# Aptomat_power_supply.net
KiCad netlist of a schematic drawn in Altium Designer
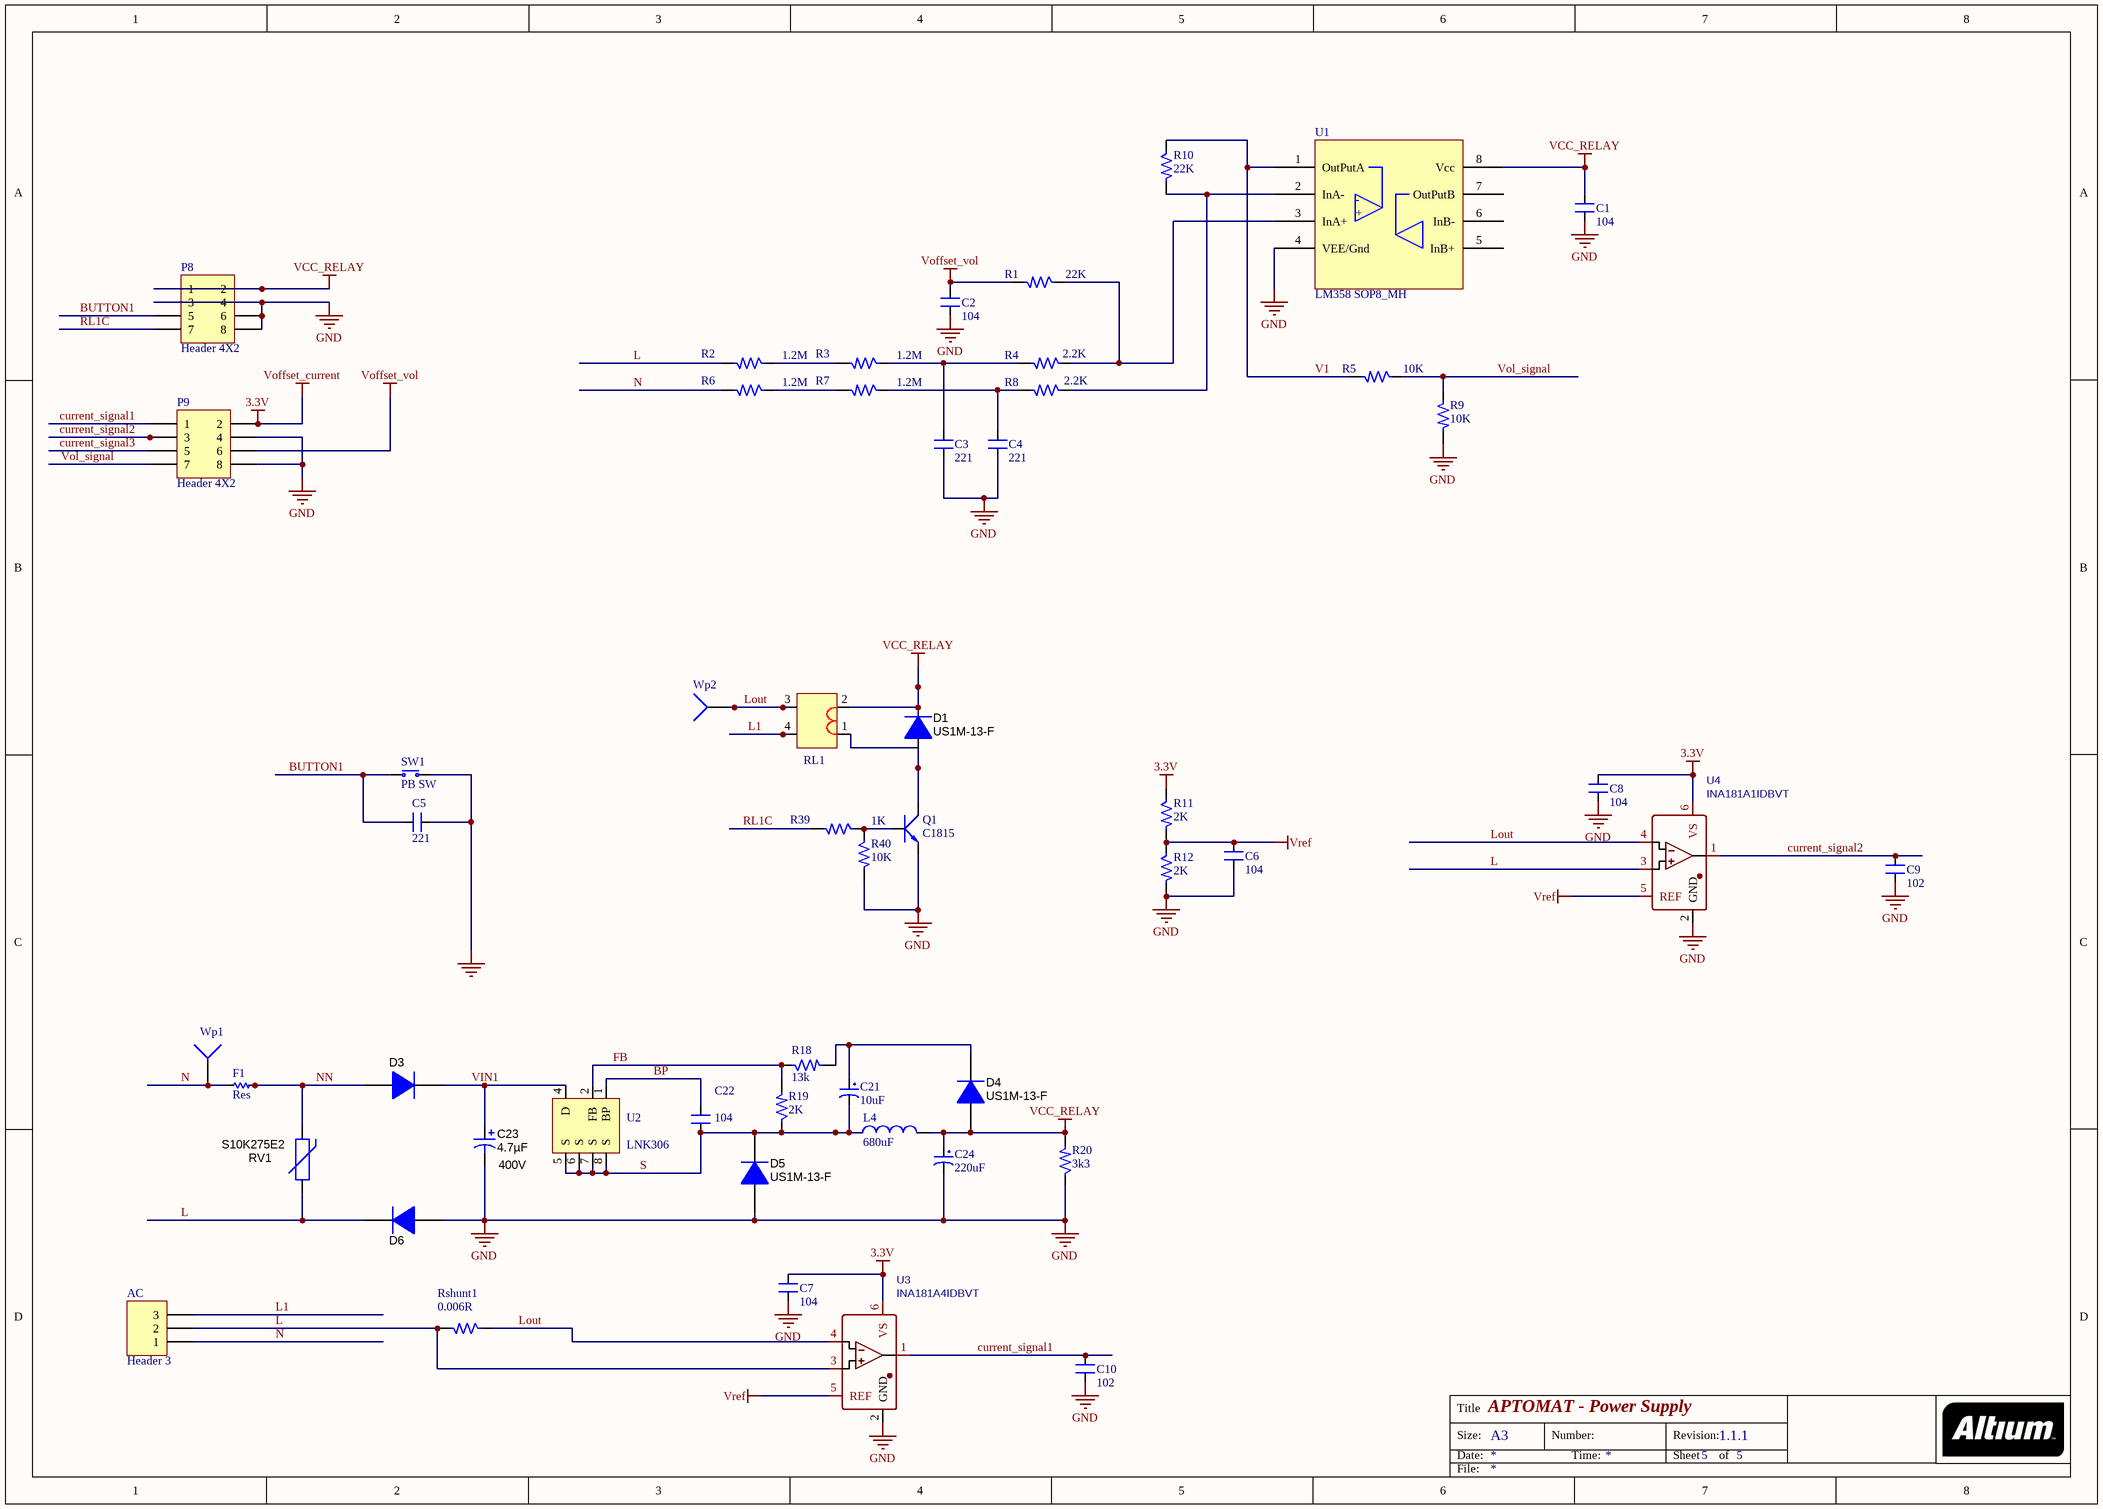
[diagram p0: Aptomat_power_supply.SchDoc]

(export (version "E")
  (design (tool "Eeschema 10.0.6"))
  (components
    (comp (ref "AC")
      (value "Header 3")
      (footprint "CHAN3DONG")
      (description "Header, 3-Pin")
      (fields (field (name "PUBLISHER") "Altium Limited"))
      (libsource (lib "Miscellaneous Connectors") (part "Header 3"))
    )
    (comp (ref "C1")
      (value "104")
      (footprint "0805_HV")
      (description "Cap SMD")
      (libsource (lib "hatcatbietbay") (part "CM"))
    )
    (comp (ref "C2")
      (value "104")
      (footprint "0805_HV")
      (description "Cap SMD")
      (libsource (lib "hatcatbietbay") (part "CM"))
    )
    (comp (ref "C3")
      (value "221")
      (footprint "0805_HV")
      (description "Cap SMD")
      (libsource (lib "hatcatbietbay") (part "CM"))
    )
    (comp (ref "C4")
      (value "221")
      (footprint "0805_HV")
      (description "Cap SMD")
      (libsource (lib "hatcatbietbay") (part "CM"))
    )
    (comp (ref "C5")
      (value "221")
      (footprint "0805_HV")
      (description "Cap SMD")
      (libsource (lib "hatcatbietbay") (part "CM"))
    )
    (comp (ref "C6")
      (value "104")
      (footprint "0805_HV")
      (description "Cap SMD")
      (libsource (lib "hatcatbietbay") (part "CM"))
    )
    (comp (ref "C7")
      (value "104")
      (footprint "0805_HV")
      (description "Cap SMD")
      (libsource (lib "hatcatbietbay") (part "CM"))
    )
    (comp (ref "C8")
      (value "104")
      (footprint "0805_HV")
      (description "Cap SMD")
      (libsource (lib "hatcatbietbay") (part "CM"))
    )
    (comp (ref "C9")
      (value "102")
      (footprint "0805_HV")
      (description "Cap SMD")
      (libsource (lib "hatcatbietbay") (part "CM"))
    )
    (comp (ref "C10")
      (value "102")
      (footprint "0805_HV")
      (description "Cap SMD")
      (libsource (lib "hatcatbietbay") (part "CM"))
    )
    (comp (ref "C21")
      (value "10uF")
      (footprint "TU_NHOM_10uF_MH")
      (description "TU_NHOM_10uF_25V_MH")
      (libsource (lib "MH_DA_THU_VIEN_16122016") (part "TU_NHOM_10uF_25V_MH"))
    )
    (comp (ref "C22")
      (value "104")
      (footprint "0805_HV")
      (description "Cap SMD")
      (libsource (lib "hatcatbietbay") (part "CM"))
    )
    (comp (ref "C23")
      (value "400AX6R8M8x11")
      (footprint "PcbLib1:PANACAP-G-GENERIC")
      (description "CAP, AL, 6.8uF, 400V, +/-20%, TH")
      (fields
        (field (name "VALUEDISPLAYED") "4.7µF")
        (field (name "MANUFACTURER") "Rubycon")
        (field (name "VALUE2") "400V")
        (field (name "PUBLISHER") "Texas Instruments")
      )
      (libsource (lib "Capacitor_Aluminum") (part "400AX6R8M8x11"))
    )
    (comp (ref "C24")
      (value "220uF")
      (footprint "TU_NHOM_2.5_MH")
      (description "TU_NHOM_220uF_25V_MH")
      (libsource (lib "MH_DA_THU_VIEN_16122016") (part "TU_NHOM_220uF_25V_MH"))
    )
    (comp (ref "D1")
      (value "US1M-13-F")
      (footprint "PcbLib1:SMB")
      (description "Diode, Ultrafast, 600V, 1A, SMB")
      (fields
        (field (name "PARTNUMBER") "US1M-13-F")
        (field (name "MANUFACTURER") "Diodes Inc.")
        (field (name "PUBLISHER") "Texas Instruments")
      )
      (libsource (lib "Diode") (part "MURS160-13-F"))
    )
    (comp (ref "D3")
      (value "US1M-13-F")
      (footprint "PcbLib1:SMB")
      (description "Diode, Ultrafast, 600V, 1A, SMB")
      (fields (field (name "MANUFACTURER") "Diodes Inc.") (field (name "PUBLISHER") "Texas Instruments"))
      (libsource (lib "Diode") (part "MURS160-13-F"))
    )
    (comp (ref "D4")
      (value "US1M-13-F")
      (footprint "PcbLib1:SMB")
      (description "Diode, Ultrafast, 600V, 1A, SMB")
      (fields
        (field (name "PARTNUMBER") "US1M-13-F")
        (field (name "MANUFACTURER") "Diodes Inc.")
        (field (name "PUBLISHER") "Texas Instruments")
      )
      (libsource (lib "Diode") (part "MURS160-13-F"))
    )
    (comp (ref "D5")
      (value "US1M-13-F")
      (footprint "PcbLib1:SMB")
      (description "Diode, Ultrafast, 600V, 1A, SMB")
      (fields
        (field (name "PARTNUMBER") "US1M-13-F")
        (field (name "MANUFACTURER") "Diodes Inc.")
        (field (name "PUBLISHER") "Texas Instruments")
      )
      (libsource (lib "Diode") (part "MURS160-13-F"))
    )
    (comp (ref "D6")
      (value "US1M-13-F")
      (footprint "PcbLib1:SMB")
      (description "Diode, Ultrafast, 600V, 1A, SMB")
      (fields (field (name "MANUFACTURER") "Diodes Inc.") (field (name "PUBLISHER") "Texas Instruments"))
      (libsource (lib "Diode") (part "MURS160-13-F"))
    )
    (comp (ref "F1")
      (value "Res")
      (footprint "1206")
      (description "Resistor")
      (fields
        (field (name "MANUFACTURER") "Generic Components")
        (field (name "PUBLISHER") "Altium Hobart Technology Centre")
      )
      (libsource (lib "LIBRARY") (part "Res-SMD"))
    )
    (comp (ref "L4")
      (value "680uF")
      (footprint "Inductor 4.5x5")
      (libsource (lib "MH_DA_THU_VIEN_16122016") (part "Inductor 4.5x5_MH"))
    )
    (comp (ref "P8")
      (value "Header 4X2")
      (footprint "HDR2X4")
      (description "Header, 4-Pin, Dual row")
      (fields (field (name "PUBLISHER") "Altium Limited"))
      (libsource (lib "Miscellaneous Connectors") (part "Header 4X2"))
    )
    (comp (ref "P9")
      (value "Header 4X2")
      (footprint "HDR2X4")
      (description "Header, 4-Pin, Dual row")
      (fields (field (name "PUBLISHER") "Altium Limited"))
      (libsource (lib "Miscellaneous Connectors") (part "Header 4X2"))
    )
    (comp (ref "Q1")
      (value "C1815")
      (footprint "SOT23B")
      (description "NPN 600mW, ECB")
      (libsource (lib "hatcatbietbay") (part "C1815"))
    )
    (comp (ref "R1")
      (value "22K")
      (footprint "0805_HV")
      (description "Resistor 1/4W")
      (libsource (lib "hatcatbietbay") (part "R"))
    )
    (comp (ref "R2")
      (value "1.2M")
      (footprint "1206")
      (description "Resistor 1/4W")
      (libsource (lib "hatcatbietbay") (part "R"))
    )
    (comp (ref "R3")
      (value "1.2M")
      (footprint "1206")
      (description "Resistor 1/4W")
      (libsource (lib "hatcatbietbay") (part "R"))
    )
    (comp (ref "R4")
      (value "2.2K")
      (footprint "0805_HV")
      (description "Resistor 1/4W")
      (libsource (lib "hatcatbietbay") (part "R"))
    )
    (comp (ref "R5")
      (value "10K")
      (footprint "0805_HV")
      (description "Resistor 1/4W")
      (libsource (lib "hatcatbietbay") (part "R"))
    )
    (comp (ref "R6")
      (value "1.2M")
      (footprint "1206")
      (description "Resistor 1/4W")
      (libsource (lib "hatcatbietbay") (part "R"))
    )
    (comp (ref "R7")
      (value "1.2M")
      (footprint "1206")
      (description "Resistor 1/4W")
      (libsource (lib "hatcatbietbay") (part "R"))
    )
    (comp (ref "R8")
      (value "2.2K")
      (footprint "0805_HV")
      (description "Resistor 1/4W")
      (libsource (lib "hatcatbietbay") (part "R"))
    )
    (comp (ref "R9")
      (value "10K")
      (footprint "0805_HV")
      (description "Resistor 1/4W")
      (libsource (lib "hatcatbietbay") (part "R"))
    )
    (comp (ref "R10")
      (value "22K")
      (footprint "0805_HV")
      (description "Resistor 1/4W")
      (libsource (lib "hatcatbietbay") (part "R"))
    )
    (comp (ref "R11")
      (value "2K")
      (footprint "0805_HV")
      (description "Resistor 1/4W")
      (libsource (lib "hatcatbietbay") (part "R"))
    )
    (comp (ref "R12")
      (value "2K")
      (footprint "0805_HV")
      (description "Resistor 1/4W")
      (libsource (lib "hatcatbietbay") (part "R"))
    )
    (comp (ref "R18")
      (value "13k")
      (footprint "0805_HV")
      (description "Resistor 1/4W")
      (libsource (lib "hatcatbietbay") (part "R"))
    )
    (comp (ref "R19")
      (value "2K")
      (footprint "0805_HV")
      (description "Resistor 1/4W")
      (libsource (lib "hatcatbietbay") (part "R"))
    )
    (comp (ref "R20")
      (value "3k3")
      (footprint "0805_HV")
      (description "Resistor 1/4W")
      (libsource (lib "hatcatbietbay") (part "R"))
    )
    (comp (ref "R39")
      (value "1K")
      (footprint "0805_HV")
      (description "Resistor 1/4W")
      (libsource (lib "hatcatbietbay") (part "R"))
    )
    (comp (ref "R40")
      (value "10K")
      (footprint "0805_HV")
      (description "Resistor 1/4W")
      (libsource (lib "hatcatbietbay") (part "R"))
    )
    (comp (ref "RL1")
      (value "Component_1")
      (footprint "RELAY30ASLA12VDC")
      (libsource (lib "Zettler") (part "Component_1"))
    )
    (comp (ref "Rshunt1")
      (value "0.006R")
      (footprint "RESC2728")
      (description "Resistor 1/4W")
      (libsource (lib "hatcatbietbay") (part "R"))
    )
    (comp (ref "RV1")
      (value "S10K275E2")
      (footprint "PcbLib1:VAR_S10K275E2")
      (description "Varistor 275V RMS 10MM Radial, TH")
      (fields
        (field (name "MANUFACTURER") "EPCOS Inc")
        (field (name "SYMBOLCREATOR") "a0412235")
        (field (name "PUBLISHER") "Texas Instruments")
      )
      (libsource (lib "Other_Passive") (part "S10K275E2"))
    )
    (comp (ref "SW1")
      (value "PB SW")
      (footprint "Switch-PB-6.2x6.3mm-SMD")
      (description "Tactile Switch, SPNO, SMD, 160gf, 6.2x6.3x2.5mm")
      (fields
        (field (name "PART NUMBER") "Switch-PB-6.2x6.3mm-SMD")
        (field (name "MANUFACTURER") "Dailywell")
        (field (name "PUBLISHER") "Nordic Semiconductor")
      )
      (libsource (lib "Nordic Discrete DB") (part "SW-PB"))
    )
    (comp (ref "U1")
      (value "LM358 SOP8_MH")
      (footprint "SOP 8")
      (libsource (lib "MH_DA_THU_VIEN_16122016") (part "LM358 SOP8_MH"))
    )
    (comp (ref "U2") (value "LNK306") (footprint "SOP 7") (libsource (lib "LNK304") (part "Component_1")))
    (comp (ref "U3")
      (value "INA181A4IDBVT")
      (footprint "SOT95P280X145-6N")
      (fields
        (field (name "BOM_SUPPLIER PART") "C116200")
        (field (name "BOM_MANUFACTURER PART") "INA181A2IDBVT")
        (field (name "CONTRIBUTOR") "LCSC")
      )
      (libsource (lib "Schlib1") (part "INA181"))
    )
    (comp (ref "U4")
      (value "INA181A1IDBVT")
      (footprint "SOT95P280X145-6N")
      (fields
        (field (name "BOM_SUPPLIER PART") "C116200")
        (field (name "BOM_MANUFACTURER PART") "INA181A2IDBVT")
        (field (name "CONTRIBUTOR") "LCSC")
      )
      (libsource (lib "Schlib1") (part "INA181"))
    )
    (comp (ref "Wp1")
      (value "Socket")
      (footprint "PIN1")
      (fields (field (name "PUBLISHER") "Altium Limited"))
      (libsource (lib "Miscellaneous Connectors") (part "Socket"))
    )
    (comp (ref "Wp2")
      (value "Socket")
      (footprint "PIN1")
      (fields (field (name "PUBLISHER") "Altium Limited"))
      (libsource (lib "Miscellaneous Connectors") (part "Socket"))
    )
  )
  (nets
    (net (code "1") (name "/BP") (class "Default")
      (node (ref "C22") (pin "2") (pinfunction "2_2") (pintype "passive"))
      (node (ref "U2") (pin "1") (pinfunction "BP_1") (pintype "passive"))
    )
    (net (code "2") (name "/BUTTON1") (class "Default")
      (node (ref "C5") (pin "2") (pinfunction "2_2") (pintype "passive"))
      (node (ref "P8") (pin "5") (pinfunction "5_5") (pintype "passive"))
      (node (ref "SW1") (pin "2") (pinfunction "COM_2") (pintype "passive"))
    )
    (net (code "3") (name "/FB") (class "Default")
      (node (ref "R18") (pin "1") (pinfunction "1_1") (pintype "passive"))
      (node (ref "R19") (pin "2") (pinfunction "2_2") (pintype "passive"))
      (node (ref "U2") (pin "2") (pinfunction "FB_2") (pintype "passive"))
    )
    (net (code "4") (name "/L") (class "Default")
      (node (ref "AC") (pin "2") (pinfunction "2_2") (pintype "passive"))
      (node (ref "D6") (pin "1") (pinfunction "K_1") (pintype "passive"))
      (node (ref "R2") (pin "2") (pinfunction "2_2") (pintype "passive"))
      (node (ref "RV1") (pin "1") (pinfunction "1_1") (pintype "passive"))
      (node (ref "Rshunt1") (pin "2") (pinfunction "2_2") (pintype "passive"))
      (node (ref "U3") (pin "3") (pinfunction "IN+_3") (pintype "passive"))
      (node (ref "U4") (pin "3") (pinfunction "IN+_3") (pintype "passive"))
    )
    (net (code "5") (name "/L1") (class "Default")
      (node (ref "AC") (pin "3") (pinfunction "3_3") (pintype "passive"))
      (node (ref "RL1") (pin "4") (pintype "passive"))
    )
    (net (code "6") (name "/Lout") (class "Default")
      (node (ref "RL1") (pin "3") (pintype "passive"))
      (node (ref "Rshunt1") (pin "1") (pinfunction "1_1") (pintype "passive"))
      (node (ref "U3") (pin "4") (pinfunction "IN-_4") (pintype "passive"))
      (node (ref "U4") (pin "4") (pinfunction "IN-_4") (pintype "passive"))
      (node (ref "Wp2") (pin "1") (pinfunction "1_1") (pintype "passive"))
    )
    (net (code "7") (name "/N") (class "Default")
      (node (ref "AC") (pin "1") (pinfunction "1_1") (pintype "passive"))
      (node (ref "F1") (pin "2") (pinfunction "2_2") (pintype "passive"))
      (node (ref "R6") (pin "2") (pinfunction "2_2") (pintype "passive"))
      (node (ref "Wp1") (pin "1") (pinfunction "1_1") (pintype "passive"))
    )
    (net (code "8") (name "/NN") (class "Default")
      (node (ref "D3") (pin "2") (pinfunction "A_2") (pintype "passive"))
      (node (ref "F1") (pin "1") (pinfunction "1_1") (pintype "passive"))
      (node (ref "RV1") (pin "2") (pinfunction "2_2") (pintype "passive"))
    )
    (net (code "9") (name "/RL1C") (class "Default")
      (node (ref "P8") (pin "7") (pinfunction "7_7") (pintype "passive"))
      (node (ref "R39") (pin "2") (pinfunction "2_2") (pintype "passive"))
    )
    (net (code "10") (name "/S") (class "Default")
      (node (ref "C21") (pin "2") (pinfunction "2_2") (pintype "passive"))
      (node (ref "C22") (pin "1") (pinfunction "1_1") (pintype "passive"))
      (node (ref "D5") (pin "1") (pinfunction "K_1") (pintype "passive"))
      (node (ref "L4") (pin "1") (pinfunction "1_1") (pintype "passive"))
      (node (ref "R19") (pin "1") (pinfunction "1_1") (pintype "passive"))
      (node (ref "U2") (pin "5") (pinfunction "S_5") (pintype "passive"))
      (node (ref "U2") (pin "6") (pinfunction "S_6") (pintype "passive"))
      (node (ref "U2") (pin "7") (pinfunction "S_7") (pintype "passive"))
      (node (ref "U2") (pin "8") (pinfunction "S_8") (pintype "passive"))
    )
    (net (code "11") (name "/V1") (class "Default")
      (node (ref "R10") (pin "1") (pinfunction "1_1") (pintype "passive"))
      (node (ref "R5") (pin "2") (pinfunction "2_2") (pintype "passive"))
      (node (ref "U1") (pin "1") (pinfunction "OutPutA_1") (pintype "passive"))
    )
    (net (code "12") (name "/VIN1") (class "Default")
      (node (ref "C23") (pin "1") (pinfunction "+_1") (pintype "passive"))
      (node (ref "D3") (pin "1") (pinfunction "K_1") (pintype "passive"))
      (node (ref "U2") (pin "4") (pinfunction "D_4") (pintype "passive"))
    )
    (net (code "13") (name "/Vol_signal") (class "Default")
      (node (ref "P9") (pin "7") (pinfunction "7_7") (pintype "passive"))
      (node (ref "R5") (pin "1") (pinfunction "1_1") (pintype "passive"))
      (node (ref "R9") (pin "1") (pinfunction "1_1") (pintype "passive"))
    )
    (net (code "14") (name "/current_signal1") (class "Default")
      (node (ref "C10") (pin "2") (pinfunction "2_2") (pintype "passive"))
      (node (ref "P9") (pin "1") (pinfunction "1_1") (pintype "passive"))
      (node (ref "U3") (pin "1") (pinfunction "OUT_1") (pintype "passive"))
    )
    (net (code "15") (name "/current_signal2") (class "Default")
      (node (ref "C9") (pin "2") (pinfunction "2_2") (pintype "passive"))
      (node (ref "P9") (pin "3") (pinfunction "3_3") (pintype "passive"))
      (node (ref "U4") (pin "1") (pinfunction "OUT_1") (pintype "passive"))
    )
    (net (code "16") (name "/current_signal3") (class "Default")
      (node (ref "P9") (pin "5") (pinfunction "5_5") (pintype "passive"))
    )
    (net (code "17") (name "3.3V") (class "Default")
      (node (ref "C7") (pin "2") (pinfunction "2_2") (pintype "passive"))
      (node (ref "C8") (pin "2") (pinfunction "2_2") (pintype "passive"))
      (node (ref "P9") (pin "2") (pinfunction "2_2") (pintype "passive"))
      (node (ref "R11") (pin "1") (pinfunction "1_1") (pintype "passive"))
      (node (ref "U3") (pin "6") (pinfunction "VS_6") (pintype "passive"))
      (node (ref "U4") (pin "6") (pinfunction "VS_6") (pintype "passive"))
    )
    (net (code "18") (name "GND") (class "Default")
      (node (ref "C1") (pin "1") (pinfunction "1_1") (pintype "passive"))
      (node (ref "C10") (pin "1") (pinfunction "1_1") (pintype "passive"))
      (node (ref "C2") (pin "1") (pinfunction "1_1") (pintype "passive"))
      (node (ref "C23") (pin "2") (pinfunction "-_2") (pintype "passive"))
      (node (ref "C24") (pin "2") (pinfunction "2_2") (pintype "passive"))
      (node (ref "C3") (pin "1") (pinfunction "1_1") (pintype "passive"))
      (node (ref "C4") (pin "1") (pinfunction "1_1") (pintype "passive"))
      (node (ref "C5") (pin "1") (pinfunction "1_1") (pintype "passive"))
      (node (ref "C6") (pin "1") (pinfunction "1_1") (pintype "passive"))
      (node (ref "C7") (pin "1") (pinfunction "1_1") (pintype "passive"))
      (node (ref "C8") (pin "1") (pinfunction "1_1") (pintype "passive"))
      (node (ref "C9") (pin "1") (pinfunction "1_1") (pintype "passive"))
      (node (ref "D5") (pin "2") (pinfunction "A_2") (pintype "passive"))
      (node (ref "D6") (pin "2") (pinfunction "A_2") (pintype "passive"))
      (node (ref "P8") (pin "3") (pinfunction "3_3") (pintype "passive"))
      (node (ref "P8") (pin "4") (pinfunction "4_4") (pintype "passive"))
      (node (ref "P8") (pin "6") (pinfunction "6_6") (pintype "passive"))
      (node (ref "P8") (pin "8") (pinfunction "8_8") (pintype "passive"))
      (node (ref "P9") (pin "4") (pinfunction "4_4") (pintype "passive"))
      (node (ref "P9") (pin "8") (pinfunction "8_8") (pintype "passive"))
      (node (ref "Q1") (pin "3") (pinfunction "E_3") (pintype "passive"))
      (node (ref "R12") (pin "2") (pinfunction "2_2") (pintype "passive"))
      (node (ref "R20") (pin "1") (pinfunction "1_1") (pintype "passive"))
      (node (ref "R40") (pin "2") (pinfunction "2_2") (pintype "passive"))
      (node (ref "R9") (pin "2") (pinfunction "2_2") (pintype "passive"))
      (node (ref "SW1") (pin "1") (pinfunction "N.O_1") (pintype "passive"))
      (node (ref "U1") (pin "4") (pinfunction "VEE/Gnd_4") (pintype "passive"))
      (node (ref "U3") (pin "2") (pinfunction "GND_2") (pintype "passive"))
      (node (ref "U4") (pin "2") (pinfunction "GND_2") (pintype "passive"))
    )
    (net (code "19") (name "Net-(C3-Pad2)") (class "Default")
      (node (ref "C3") (pin "2") (pinfunction "2_2") (pintype "passive"))
      (node (ref "R3") (pin "1") (pinfunction "1_1") (pintype "passive"))
      (node (ref "R4") (pin "2") (pinfunction "2_2") (pintype "passive"))
    )
    (net (code "20") (name "Net-(C4-Pad2)") (class "Default")
      (node (ref "C4") (pin "2") (pinfunction "2_2") (pintype "passive"))
      (node (ref "R7") (pin "1") (pinfunction "1_1") (pintype "passive"))
      (node (ref "R8") (pin "2") (pinfunction "2_2") (pintype "passive"))
    )
    (net (code "21") (name "Net-(D1-A)") (class "Default")
      (node (ref "D1") (pin "2") (pinfunction "A_2") (pintype "passive"))
      (node (ref "Q1") (pin "2") (pinfunction "C_2") (pintype "passive"))
      (node (ref "RL1") (pin "1") (pintype "passive"))
    )
    (net (code "22") (name "Net-(D4-K)") (class "Default")
      (node (ref "C21") (pin "1") (pinfunction "1_1") (pintype "passive"))
      (node (ref "D4") (pin "1") (pinfunction "K_1") (pintype "passive"))
      (node (ref "R18") (pin "2") (pinfunction "2_2") (pintype "passive"))
    )
    (net (code "23") (name "Net-(Q1-B)") (class "Default")
      (node (ref "Q1") (pin "1") (pinfunction "B_1") (pintype "passive"))
      (node (ref "R39") (pin "1") (pinfunction "1_1") (pintype "passive"))
      (node (ref "R40") (pin "1") (pinfunction "1_1") (pintype "passive"))
    )
    (net (code "24") (name "Net-(R2-Pad1)") (class "Default")
      (node (ref "R2") (pin "1") (pinfunction "1_1") (pintype "passive"))
      (node (ref "R3") (pin "2") (pinfunction "2_2") (pintype "passive"))
    )
    (net (code "25") (name "Net-(R6-Pad1)") (class "Default")
      (node (ref "R6") (pin "1") (pinfunction "1_1") (pintype "passive"))
      (node (ref "R7") (pin "2") (pinfunction "2_2") (pintype "passive"))
    )
    (net (code "26") (name "Net-(U1-InA+)") (class "Default")
      (node (ref "R1") (pin "1") (pinfunction "1_1") (pintype "passive"))
      (node (ref "R4") (pin "1") (pinfunction "1_1") (pintype "passive"))
      (node (ref "U1") (pin "3") (pinfunction "InA+_3") (pintype "passive"))
    )
    (net (code "27") (name "Net-(U1-InA-)") (class "Default")
      (node (ref "R10") (pin "2") (pinfunction "2_2") (pintype "passive"))
      (node (ref "R8") (pin "1") (pinfunction "1_1") (pintype "passive"))
      (node (ref "U1") (pin "2") (pinfunction "InA-_2") (pintype "passive"))
    )
    (net (code "28") (name "VCC_RELAY") (class "Default")
      (node (ref "C1") (pin "2") (pinfunction "2_2") (pintype "passive"))
      (node (ref "C24") (pin "1") (pinfunction "1_1") (pintype "passive"))
      (node (ref "D1") (pin "1") (pinfunction "K_1") (pintype "passive"))
      (node (ref "D4") (pin "2") (pinfunction "A_2") (pintype "passive"))
      (node (ref "L4") (pin "2") (pinfunction "2_2") (pintype "passive"))
      (node (ref "P8") (pin "1") (pinfunction "1_1") (pintype "passive"))
      (node (ref "P8") (pin "2") (pinfunction "2_2") (pintype "passive"))
      (node (ref "R20") (pin "2") (pinfunction "2_2") (pintype "passive"))
      (node (ref "RL1") (pin "2") (pintype "passive"))
      (node (ref "U1") (pin "8") (pinfunction "Vcc_8") (pintype "passive"))
    )
    (net (code "29") (name "Voffset_vol") (class "Default")
      (node (ref "C2") (pin "2") (pinfunction "2_2") (pintype "passive"))
      (node (ref "P9") (pin "6") (pinfunction "6_6") (pintype "passive"))
      (node (ref "R1") (pin "2") (pinfunction "2_2") (pintype "passive"))
    )
    (net (code "30") (name "Vref") (class "Default")
      (node (ref "C6") (pin "2") (pinfunction "2_2") (pintype "passive"))
      (node (ref "R11") (pin "2") (pinfunction "2_2") (pintype "passive"))
      (node (ref "R12") (pin "1") (pinfunction "1_1") (pintype "passive"))
      (node (ref "U3") (pin "5") (pinfunction "REF_5") (pintype "passive"))
      (node (ref "U4") (pin "5") (pinfunction "REF_5") (pintype "passive"))
    )
    (net (code "31") (name "unconnected-(U1-InB+-Pad5)") (class "Default")
      (node (ref "U1") (pin "5") (pinfunction "InB+_5") (pintype "passive"))
    )
    (net (code "32") (name "unconnected-(U1-InB--Pad6)") (class "Default")
      (node (ref "U1") (pin "6") (pinfunction "InB-_6") (pintype "passive"))
    )
    (net (code "33") (name "unconnected-(U1-OutPutB-Pad7)") (class "Default")
      (node (ref "U1") (pin "7") (pinfunction "OutPutB_7") (pintype "passive"))
    )
  )
)
